# 780-00041_rev2_Front_Panel_Mirror_Cell_C.net
KiCad netlist of a schematic drawn in Altium Designer
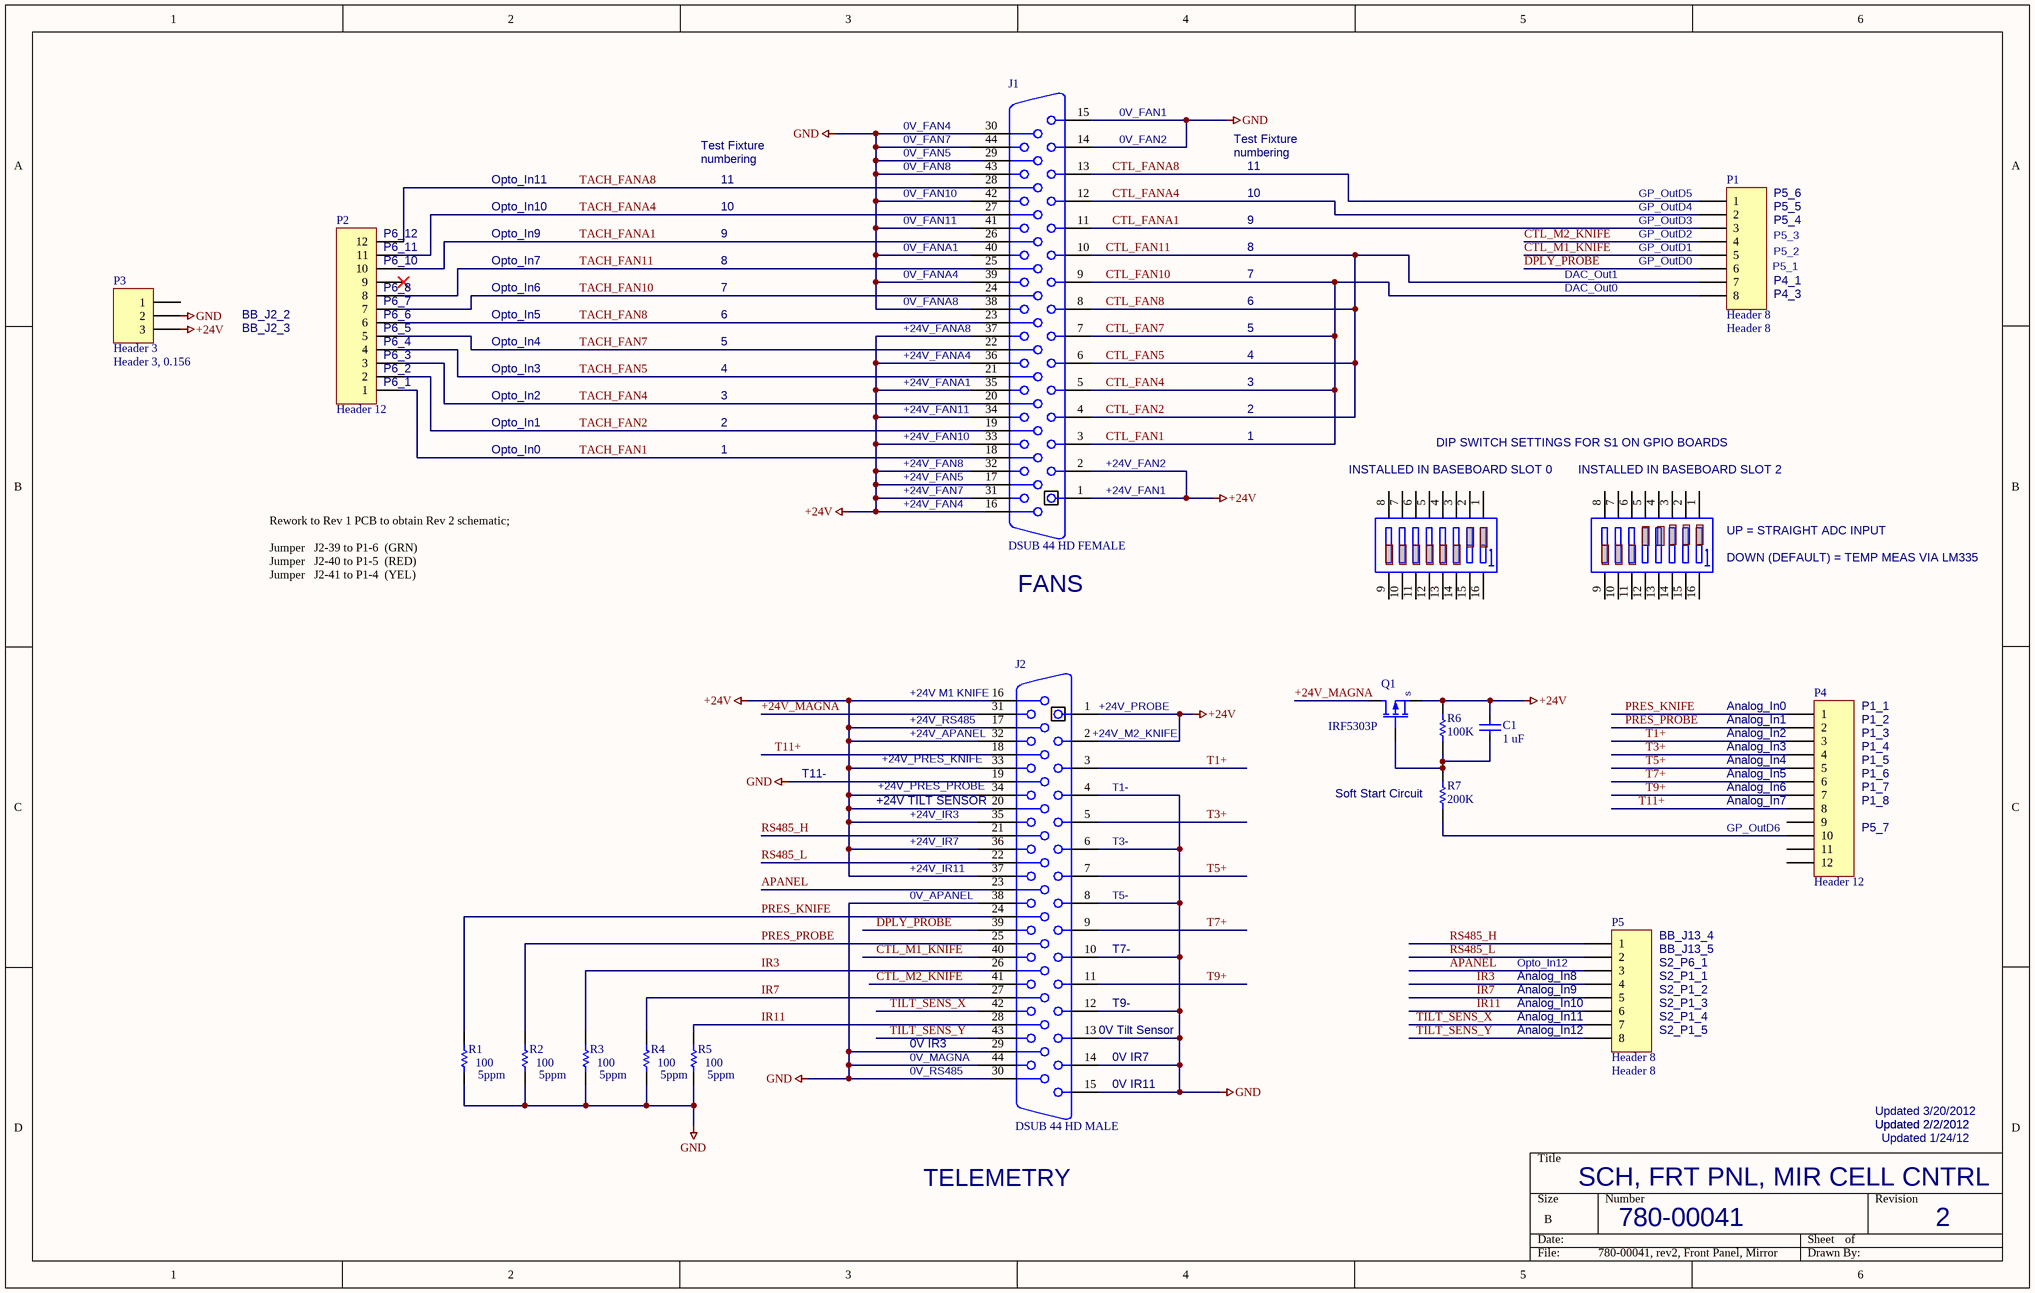
[diagram p0: 780-00041, rev2, Front Panel, Mirror Cell Controller.SchDoc]

(export (version "E")
  (design (tool "Eeschema 10.0.6"))
  (components
    (comp (ref "C1")
      (value "1 uF")
      (footprint "SMD_0805")
      (description "Capacitor")
      (fields (field (name "Comment") "Cap SMD"))
      (libsource (lib "Richs Schematic Components") (part "Cap SMD"))
    )
    (comp (ref "J1")
      (value "DSUB 44 HD FEMALE")
      (footprint "CONN DB44 HD FEM SOCKETS PCB")
      (description "Receptacle Assembly, 44 PIN")
      (fields (field (name "MANUFACTURER") "fci"))
      (libsource (lib "Richs Schematic Components") (part "DSUB 44 HD FEMALE"))
    )
    (comp (ref "J2")
      (value "DSUB 44 HD MALE")
      (footprint "CONN DB44 HD MALE PINS PCB")
      (description "Receptacle Assembly, 44 PIN")
      (fields (field (name "MANUFACTURER") "FCI"))
      (libsource (lib "Richs Schematic Components") (part "DSUB 44 HD MALE"))
    )
    (comp (ref "P1")
      (value "Header 8")
      (footprint "HDR1X8 for IDC")
      (description "Header, 8-Pin")
      (fields (field (name "MANUFACTURER") "tyco") (field (name "ALTIUM_VALUE") "Header 8"))
      (libsource (lib "Richs Schematic Components") (part "Header 8"))
    )
    (comp (ref "P2")
      (value "Header 12")
      (footprint "HDR1X12 for IDC")
      (description "Header, 12-Pin")
      (fields (field (name "MANUFACTURER") "Tyco"))
      (libsource (lib "") (part "Header 12_1"))
    )
    (comp (ref "P3")
      (value "Header 3")
      (footprint "HDR 1X3 0.156\"")
      (description "Header, 3-Pin, 0.156")
      (fields (field (name "ALTIUM_VALUE") "Header 3, 0.156"))
      (libsource (lib "Richs Schematic Components") (part "Header 3, 0.156"))
    )
    (comp (ref "P4")
      (value "Header 12")
      (footprint "HDR1X12 for IDC")
      (description "Header, 12-Pin")
      (fields (field (name "MANUFACTURER") "Tyco"))
      (libsource (lib "Richs Schematic Components") (part "Header 12"))
    )
    (comp (ref "P5")
      (value "Header 8")
      (footprint "HDR1X8 for IDC")
      (description "Header, 8-Pin")
      (fields (field (name "MANUFACTURER") "tyco") (field (name "ALTIUM_VALUE") "Header 8"))
      (libsource (lib "Richs Schematic Components") (part "Header 8"))
    )
    (comp (ref "Q1")
      (value "IRF5303P")
      (footprint "TO-252(D-PAK)  PowerPAD")
      (description "P-Chan MOSFET")
      (fields (field (name "MANUFACTURER") "INT'l Rectifier"))
      (libsource (lib "Richs Schematic Components") (part "IRF5303P"))
    )
    (comp (ref "R1")
      (value "5ppm")
      (footprint "SMD_0805")
      (description "Resistor 0805")
      (fields (field (name "MANUFACTURER") "Vishay/Dale") (field (name "ALTIUM_VALUE") "100"))
      (libsource (lib "Richs Schematic Components") (part "Res SMD"))
    )
    (comp (ref "R2")
      (value "5ppm")
      (footprint "SMD_0805")
      (description "Resistor 0805")
      (fields (field (name "MANUFACTURER") "Vishay/Dale") (field (name "ALTIUM_VALUE") "100"))
      (libsource (lib "Richs Schematic Components") (part "Res SMD"))
    )
    (comp (ref "R3")
      (value "5ppm")
      (footprint "SMD_0805")
      (description "Resistor 0805")
      (fields (field (name "MANUFACTURER") "Vishay/Dale") (field (name "ALTIUM_VALUE") "100"))
      (libsource (lib "Richs Schematic Components") (part "Res SMD"))
    )
    (comp (ref "R4")
      (value "5ppm")
      (footprint "SMD_0805")
      (description "Resistor 0805")
      (fields (field (name "MANUFACTURER") "Vishay/Dale") (field (name "ALTIUM_VALUE") "100"))
      (libsource (lib "Richs Schematic Components") (part "Res SMD"))
    )
    (comp (ref "R5")
      (value "5ppm")
      (footprint "SMD_0805")
      (description "Resistor 0805")
      (fields (field (name "MANUFACTURER") "Vishay/Dale") (field (name "ALTIUM_VALUE") "100"))
      (libsource (lib "Richs Schematic Components") (part "Res SMD"))
    )
    (comp (ref "R6")
      (value "100K")
      (footprint "SMD_0805")
      (description "Resistor 0805")
      (fields (field (name "MANUFACTURER") "Vishay/Dale") (field (name "Comment") "Res 0805"))
      (libsource (lib "Richs Schematic Components") (part "Res SMD"))
    )
    (comp (ref "R7")
      (value "200K")
      (footprint "SMD_0805")
      (description "Resistor 0805")
      (fields (field (name "MANUFACTURER") "Vishay/Dale") (field (name "Comment") "Res 0805"))
      (libsource (lib "Richs Schematic Components") (part "Res SMD"))
    )
    (comp (ref "S100")
      (value "SW DIP-8")
      (footprint "DIP_SW_8WAY_SMD")
      (description "DIP Switch, 8 Position, SPST")
      (fields (field (name "PUBLISHER") "Altium Limited"))
      (libsource (lib "Miscellaneous Devices") (part "SW DIP-8"))
    )
    (comp (ref "S101")
      (value "SW DIP-8")
      (footprint "DIP_SW_8WAY_SMD")
      (description "DIP Switch, 8 Position, SPST")
      (fields (field (name "PUBLISHER") "Altium Limited"))
      (libsource (lib "Miscellaneous Devices") (part "SW DIP-8"))
    )
  )
  (nets
    (net (code "1") (name "+24V") (class "Default")
      (node (ref "C1") (pin "2") (pinfunction "2_2") (pintype "passive"))
      (node (ref "J1") (pin "1") (pintype "passive"))
      (node (ref "J1") (pin "16") (pintype "passive"))
      (node (ref "J1") (pin "17") (pintype "passive"))
      (node (ref "J1") (pin "2") (pintype "passive"))
      (node (ref "J1") (pin "31") (pintype "passive"))
      (node (ref "J1") (pin "32") (pintype "passive"))
      (node (ref "J1") (pin "33") (pintype "passive"))
      (node (ref "J1") (pin "34") (pintype "passive"))
      (node (ref "J1") (pin "35") (pintype "passive"))
      (node (ref "J1") (pin "36") (pintype "passive"))
      (node (ref "J1") (pin "37") (pintype "passive"))
      (node (ref "J2") (pin "1") (pintype "passive"))
      (node (ref "J2") (pin "16") (pintype "passive"))
      (node (ref "J2") (pin "17") (pintype "passive"))
      (node (ref "J2") (pin "2") (pintype "passive"))
      (node (ref "J2") (pin "20") (pintype "passive"))
      (node (ref "J2") (pin "32") (pintype "passive"))
      (node (ref "J2") (pin "33") (pintype "passive"))
      (node (ref "J2") (pin "34") (pintype "passive"))
      (node (ref "J2") (pin "35") (pintype "passive"))
      (node (ref "J2") (pin "36") (pintype "passive"))
      (node (ref "J2") (pin "37") (pintype "passive"))
      (node (ref "P3") (pin "3") (pinfunction "3_3") (pintype "passive"))
      (node (ref "Q1") (pin "3") (pinfunction "S_3") (pintype "passive"))
      (node (ref "R6") (pin "2") (pinfunction "2_2") (pintype "passive"))
    )
    (net (code "2") (name "/+24V_MAGNA") (class "Default")
      (node (ref "J2") (pin "31") (pintype "passive"))
      (node (ref "Q1") (pin "2") (pinfunction "D_2") (pintype "passive"))
    )
    (net (code "3") (name "/APANEL") (class "Default")
      (node (ref "J2") (pin "23") (pintype "passive"))
      (node (ref "P5") (pin "3") (pinfunction "3_3") (pintype "passive"))
    )
    (net (code "4") (name "/CTL_FAN1") (class "Default")
      (node (ref "J1") (pin "3") (pintype "passive"))
      (node (ref "J1") (pin "5") (pintype "passive"))
      (node (ref "J1") (pin "7") (pintype "passive"))
      (node (ref "J1") (pin "9") (pintype "passive"))
      (node (ref "P1") (pin "8") (pinfunction "8_8") (pintype "passive"))
    )
    (net (code "5") (name "/CTL_FAN11") (class "Default")
      (node (ref "J1") (pin "10") (pintype "passive"))
      (node (ref "J1") (pin "4") (pintype "passive"))
      (node (ref "J1") (pin "6") (pintype "passive"))
      (node (ref "J1") (pin "8") (pintype "passive"))
      (node (ref "P1") (pin "7") (pinfunction "7_7") (pintype "passive"))
    )
    (net (code "6") (name "/CTL_FANA1") (class "Default")
      (node (ref "J1") (pin "11") (pintype "passive"))
      (node (ref "P1") (pin "3") (pinfunction "3_3") (pintype "passive"))
    )
    (net (code "7") (name "/CTL_FANA4") (class "Default")
      (node (ref "J1") (pin "12") (pintype "passive"))
      (node (ref "P1") (pin "2") (pinfunction "2_2") (pintype "passive"))
    )
    (net (code "8") (name "/CTL_FANA8") (class "Default")
      (node (ref "J1") (pin "13") (pintype "passive"))
      (node (ref "P1") (pin "1") (pinfunction "1_1") (pintype "passive"))
    )
    (net (code "9") (name "/CTL_M1_KNIFE") (class "Default")
      (node (ref "J2") (pin "40") (pintype "passive"))
      (node (ref "P1") (pin "5") (pinfunction "5_5") (pintype "passive"))
    )
    (net (code "10") (name "/CTL_M2_KNIFE") (class "Default")
      (node (ref "J2") (pin "41") (pintype "passive"))
      (node (ref "P1") (pin "4") (pinfunction "4_4") (pintype "passive"))
    )
    (net (code "11") (name "/DPLY_PROBE") (class "Default")
      (node (ref "J2") (pin "39") (pintype "passive"))
      (node (ref "P1") (pin "6") (pinfunction "6_6") (pintype "passive"))
    )
    (net (code "12") (name "/IR3") (class "Default")
      (node (ref "J2") (pin "26") (pintype "passive"))
      (node (ref "P5") (pin "4") (pinfunction "4_4") (pintype "passive"))
      (node (ref "R3") (pin "2") (pinfunction "2_2") (pintype "passive"))
    )
    (net (code "13") (name "/IR7") (class "Default")
      (node (ref "J2") (pin "27") (pintype "passive"))
      (node (ref "P5") (pin "5") (pinfunction "5_5") (pintype "passive"))
      (node (ref "R4") (pin "2") (pinfunction "2_2") (pintype "passive"))
    )
    (net (code "14") (name "/IR11") (class "Default")
      (node (ref "J2") (pin "28") (pintype "passive"))
      (node (ref "P5") (pin "6") (pinfunction "6_6") (pintype "passive"))
      (node (ref "R5") (pin "2") (pinfunction "2_2") (pintype "passive"))
    )
    (net (code "15") (name "/PRES_KNIFE") (class "Default")
      (node (ref "J2") (pin "24") (pintype "passive"))
      (node (ref "P4") (pin "1") (pinfunction "1_1") (pintype "passive"))
      (node (ref "R1") (pin "2") (pinfunction "2_2") (pintype "passive"))
    )
    (net (code "16") (name "/PRES_PROBE") (class "Default")
      (node (ref "J2") (pin "25") (pintype "passive"))
      (node (ref "P4") (pin "2") (pinfunction "2_2") (pintype "passive"))
      (node (ref "R2") (pin "2") (pinfunction "2_2") (pintype "passive"))
    )
    (net (code "17") (name "/RS485_H") (class "Default")
      (node (ref "J2") (pin "21") (pintype "passive"))
      (node (ref "P5") (pin "1") (pinfunction "1_1") (pintype "passive"))
    )
    (net (code "18") (name "/RS485_L") (class "Default")
      (node (ref "J2") (pin "22") (pintype "passive"))
      (node (ref "P5") (pin "2") (pinfunction "2_2") (pintype "passive"))
    )
    (net (code "19") (name "/T1+") (class "Default")
      (node (ref "J2") (pin "3") (pintype "passive"))
      (node (ref "P4") (pin "3") (pinfunction "3_3") (pintype "passive"))
    )
    (net (code "20") (name "/T3+") (class "Default")
      (node (ref "J2") (pin "5") (pintype "passive"))
      (node (ref "P4") (pin "4") (pinfunction "4_4") (pintype "passive"))
    )
    (net (code "21") (name "/T5+") (class "Default")
      (node (ref "J2") (pin "7") (pintype "passive"))
      (node (ref "P4") (pin "5") (pinfunction "5_5") (pintype "passive"))
    )
    (net (code "22") (name "/T7+") (class "Default")
      (node (ref "J2") (pin "9") (pintype "passive"))
      (node (ref "P4") (pin "6") (pinfunction "6_6") (pintype "passive"))
    )
    (net (code "23") (name "/T9+") (class "Default")
      (node (ref "J2") (pin "11") (pintype "passive"))
      (node (ref "P4") (pin "7") (pinfunction "7_7") (pintype "passive"))
    )
    (net (code "24") (name "/T11+") (class "Default")
      (node (ref "J2") (pin "18") (pintype "passive"))
      (node (ref "P4") (pin "8") (pinfunction "8_8") (pintype "passive"))
    )
    (net (code "25") (name "/TACH_FAN1") (class "Default")
      (node (ref "J1") (pin "18") (pintype "passive"))
      (node (ref "P2") (pin "1") (pinfunction "1_1") (pintype "passive"))
    )
    (net (code "26") (name "/TACH_FAN2") (class "Default")
      (node (ref "J1") (pin "19") (pintype "passive"))
      (node (ref "P2") (pin "2") (pinfunction "2_2") (pintype "passive"))
    )
    (net (code "27") (name "/TACH_FAN4") (class "Default")
      (node (ref "J1") (pin "20") (pintype "passive"))
      (node (ref "P2") (pin "3") (pinfunction "3_3") (pintype "passive"))
    )
    (net (code "28") (name "/TACH_FAN5") (class "Default")
      (node (ref "J1") (pin "21") (pintype "passive"))
      (node (ref "P2") (pin "4") (pinfunction "4_4") (pintype "passive"))
    )
    (net (code "29") (name "/TACH_FAN7") (class "Default")
      (node (ref "J1") (pin "22") (pintype "passive"))
      (node (ref "P2") (pin "5") (pinfunction "5_5") (pintype "passive"))
    )
    (net (code "30") (name "/TACH_FAN8") (class "Default")
      (node (ref "J1") (pin "23") (pintype "passive"))
      (node (ref "P2") (pin "6") (pinfunction "6_6") (pintype "passive"))
    )
    (net (code "31") (name "/TACH_FAN10") (class "Default")
      (node (ref "J1") (pin "24") (pintype "passive"))
      (node (ref "P2") (pin "7") (pinfunction "7_7") (pintype "passive"))
    )
    (net (code "32") (name "/TACH_FAN11") (class "Default")
      (node (ref "J1") (pin "25") (pintype "passive"))
      (node (ref "P2") (pin "8") (pinfunction "8_8") (pintype "passive"))
    )
    (net (code "33") (name "/TACH_FANA1") (class "Default")
      (node (ref "J1") (pin "26") (pintype "passive"))
      (node (ref "P2") (pin "10") (pinfunction "10_10") (pintype "passive"))
    )
    (net (code "34") (name "/TACH_FANA4") (class "Default")
      (node (ref "J1") (pin "27") (pintype "passive"))
      (node (ref "P2") (pin "11") (pinfunction "11_11") (pintype "passive"))
    )
    (net (code "35") (name "/TACH_FANA8") (class "Default")
      (node (ref "J1") (pin "28") (pintype "passive"))
      (node (ref "P2") (pin "12") (pinfunction "12_12") (pintype "passive"))
    )
    (net (code "36") (name "/TILT_SENS_X") (class "Default")
      (node (ref "J2") (pin "42") (pintype "passive"))
      (node (ref "P5") (pin "7") (pinfunction "7_7") (pintype "passive"))
    )
    (net (code "37") (name "/TILT_SENS_Y") (class "Default")
      (node (ref "J2") (pin "43") (pintype "passive"))
      (node (ref "P5") (pin "8") (pinfunction "8_8") (pintype "passive"))
    )
    (net (code "38") (name "GND") (class "Default")
      (node (ref "J1") (pin "14") (pintype "passive"))
      (node (ref "J1") (pin "15") (pintype "passive"))
      (node (ref "J1") (pin "29") (pintype "passive"))
      (node (ref "J1") (pin "30") (pintype "passive"))
      (node (ref "J1") (pin "38") (pintype "passive"))
      (node (ref "J1") (pin "39") (pintype "passive"))
      (node (ref "J1") (pin "40") (pintype "passive"))
      (node (ref "J1") (pin "41") (pintype "passive"))
      (node (ref "J1") (pin "42") (pintype "passive"))
      (node (ref "J1") (pin "43") (pintype "passive"))
      (node (ref "J1") (pin "44") (pintype "passive"))
      (node (ref "J2") (pin "10") (pintype "passive"))
      (node (ref "J2") (pin "12") (pintype "passive"))
      (node (ref "J2") (pin "13") (pintype "passive"))
      (node (ref "J2") (pin "14") (pintype "passive"))
      (node (ref "J2") (pin "15") (pintype "passive"))
      (node (ref "J2") (pin "19") (pintype "passive"))
      (node (ref "J2") (pin "29") (pintype "passive"))
      (node (ref "J2") (pin "30") (pintype "passive"))
      (node (ref "J2") (pin "38") (pintype "passive"))
      (node (ref "J2") (pin "4") (pintype "passive"))
      (node (ref "J2") (pin "44") (pintype "passive"))
      (node (ref "J2") (pin "6") (pintype "passive"))
      (node (ref "J2") (pin "8") (pintype "passive"))
      (node (ref "P3") (pin "2") (pinfunction "2_2") (pintype "passive"))
      (node (ref "R1") (pin "1") (pinfunction "1_1") (pintype "passive"))
      (node (ref "R2") (pin "1") (pinfunction "1_1") (pintype "passive"))
      (node (ref "R3") (pin "1") (pinfunction "1_1") (pintype "passive"))
      (node (ref "R4") (pin "1") (pinfunction "1_1") (pintype "passive"))
      (node (ref "R5") (pin "1") (pinfunction "1_1") (pintype "passive"))
    )
    (net (code "39") (name "Net-(P4-Pad10)") (class "Default")
      (node (ref "P4") (pin "10") (pinfunction "10_10") (pintype "passive"))
      (node (ref "R7") (pin "1") (pinfunction "1_1") (pintype "passive"))
    )
    (net (code "40") (name "Net-(Q1-G)") (class "Default")
      (node (ref "C1") (pin "1") (pinfunction "1_1") (pintype "passive"))
      (node (ref "Q1") (pin "1") (pinfunction "G_1") (pintype "passive"))
      (node (ref "R6") (pin "1") (pinfunction "1_1") (pintype "passive"))
      (node (ref "R7") (pin "2") (pinfunction "2_2") (pintype "passive"))
    )
    (net (code "41") (name "unconnected-(P2-Pad9)") (class "Default")
      (node (ref "P2") (pin "9") (pinfunction "9_9") (pintype "passive+no_connect"))
    )
    (net (code "42") (name "unconnected-(P3-Pad1)") (class "Default")
      (node (ref "P3") (pin "1") (pinfunction "1_1") (pintype "passive"))
    )
    (net (code "43") (name "unconnected-(P4-Pad9)") (class "Default")
      (node (ref "P4") (pin "9") (pinfunction "9_9") (pintype "passive"))
    )
    (net (code "44") (name "unconnected-(P4-Pad11)") (class "Default")
      (node (ref "P4") (pin "11") (pinfunction "11_11") (pintype "passive"))
    )
    (net (code "45") (name "unconnected-(P4-Pad12)") (class "Default")
      (node (ref "P4") (pin "12") (pinfunction "12_12") (pintype "passive"))
    )
    (net (code "46") (name "unconnected-(S100-A1-Pad1)") (class "Default")
      (node (ref "S100") (pin "1") (pinfunction "A1_1") (pintype "passive"))
    )
    (net (code "47") (name "unconnected-(S100-A2-Pad2)") (class "Default")
      (node (ref "S100") (pin "2") (pinfunction "A2_2") (pintype "passive"))
    )
    (net (code "48") (name "unconnected-(S100-A3-Pad3)") (class "Default")
      (node (ref "S100") (pin "3") (pinfunction "A3_3") (pintype "passive"))
    )
    (net (code "49") (name "unconnected-(S100-A4-Pad4)") (class "Default")
      (node (ref "S100") (pin "4") (pinfunction "A4_4") (pintype "passive"))
    )
    (net (code "50") (name "unconnected-(S100-A5-Pad5)") (class "Default")
      (node (ref "S100") (pin "5") (pinfunction "A5_5") (pintype "passive"))
    )
    (net (code "51") (name "unconnected-(S100-A6-Pad6)") (class "Default")
      (node (ref "S100") (pin "6") (pinfunction "A6_6") (pintype "passive"))
    )
    (net (code "52") (name "unconnected-(S100-A7-Pad7)") (class "Default")
      (node (ref "S100") (pin "7") (pinfunction "A7_7") (pintype "passive"))
    )
    (net (code "53") (name "unconnected-(S100-A8-Pad8)") (class "Default")
      (node (ref "S100") (pin "8") (pinfunction "A8_8") (pintype "passive"))
    )
    (net (code "54") (name "unconnected-(S100-B1-Pad16)") (class "Default")
      (node (ref "S100") (pin "16") (pinfunction "B1_16") (pintype "passive"))
    )
    (net (code "55") (name "unconnected-(S100-B2-Pad15)") (class "Default")
      (node (ref "S100") (pin "15") (pinfunction "B2_15") (pintype "passive"))
    )
    (net (code "56") (name "unconnected-(S100-B3-Pad14)") (class "Default")
      (node (ref "S100") (pin "14") (pinfunction "B3_14") (pintype "passive"))
    )
    (net (code "57") (name "unconnected-(S100-B4-Pad13)") (class "Default")
      (node (ref "S100") (pin "13") (pinfunction "B4_13") (pintype "passive"))
    )
    (net (code "58") (name "unconnected-(S100-B5-Pad12)") (class "Default")
      (node (ref "S100") (pin "12") (pinfunction "B5_12") (pintype "passive"))
    )
    (net (code "59") (name "unconnected-(S100-B6-Pad11)") (class "Default")
      (node (ref "S100") (pin "11") (pinfunction "B6_11") (pintype "passive"))
    )
    (net (code "60") (name "unconnected-(S100-B7-Pad10)") (class "Default")
      (node (ref "S100") (pin "10") (pinfunction "B7_10") (pintype "passive"))
    )
    (net (code "61") (name "unconnected-(S100-B8-Pad9)") (class "Default")
      (node (ref "S100") (pin "9") (pinfunction "B8_9") (pintype "passive"))
    )
    (net (code "62") (name "unconnected-(S101-A1-Pad1)") (class "Default")
      (node (ref "S101") (pin "1") (pinfunction "A1_1") (pintype "passive"))
    )
    (net (code "63") (name "unconnected-(S101-A2-Pad2)") (class "Default")
      (node (ref "S101") (pin "2") (pinfunction "A2_2") (pintype "passive"))
    )
    (net (code "64") (name "unconnected-(S101-A3-Pad3)") (class "Default")
      (node (ref "S101") (pin "3") (pinfunction "A3_3") (pintype "passive"))
    )
    (net (code "65") (name "unconnected-(S101-A4-Pad4)") (class "Default")
      (node (ref "S101") (pin "4") (pinfunction "A4_4") (pintype "passive"))
    )
    (net (code "66") (name "unconnected-(S101-A5-Pad5)") (class "Default")
      (node (ref "S101") (pin "5") (pinfunction "A5_5") (pintype "passive"))
    )
    (net (code "67") (name "unconnected-(S101-A6-Pad6)") (class "Default")
      (node (ref "S101") (pin "6") (pinfunction "A6_6") (pintype "passive"))
    )
    (net (code "68") (name "unconnected-(S101-A7-Pad7)") (class "Default")
      (node (ref "S101") (pin "7") (pinfunction "A7_7") (pintype "passive"))
    )
    (net (code "69") (name "unconnected-(S101-A8-Pad8)") (class "Default")
      (node (ref "S101") (pin "8") (pinfunction "A8_8") (pintype "passive"))
    )
    (net (code "70") (name "unconnected-(S101-B1-Pad16)") (class "Default")
      (node (ref "S101") (pin "16") (pinfunction "B1_16") (pintype "passive"))
    )
    (net (code "71") (name "unconnected-(S101-B2-Pad15)") (class "Default")
      (node (ref "S101") (pin "15") (pinfunction "B2_15") (pintype "passive"))
    )
    (net (code "72") (name "unconnected-(S101-B3-Pad14)") (class "Default")
      (node (ref "S101") (pin "14") (pinfunction "B3_14") (pintype "passive"))
    )
    (net (code "73") (name "unconnected-(S101-B4-Pad13)") (class "Default")
      (node (ref "S101") (pin "13") (pinfunction "B4_13") (pintype "passive"))
    )
    (net (code "74") (name "unconnected-(S101-B5-Pad12)") (class "Default")
      (node (ref "S101") (pin "12") (pinfunction "B5_12") (pintype "passive"))
    )
    (net (code "75") (name "unconnected-(S101-B6-Pad11)") (class "Default")
      (node (ref "S101") (pin "11") (pinfunction "B6_11") (pintype "passive"))
    )
    (net (code "76") (name "unconnected-(S101-B7-Pad10)") (class "Default")
      (node (ref "S101") (pin "10") (pinfunction "B7_10") (pintype "passive"))
    )
    (net (code "77") (name "unconnected-(S101-B8-Pad9)") (class "Default")
      (node (ref "S101") (pin "9") (pinfunction "B8_9") (pintype "passive"))
    )
  )
)
